# CH341A.net
KiCad netlist of a schematic drawn in Altium Designer
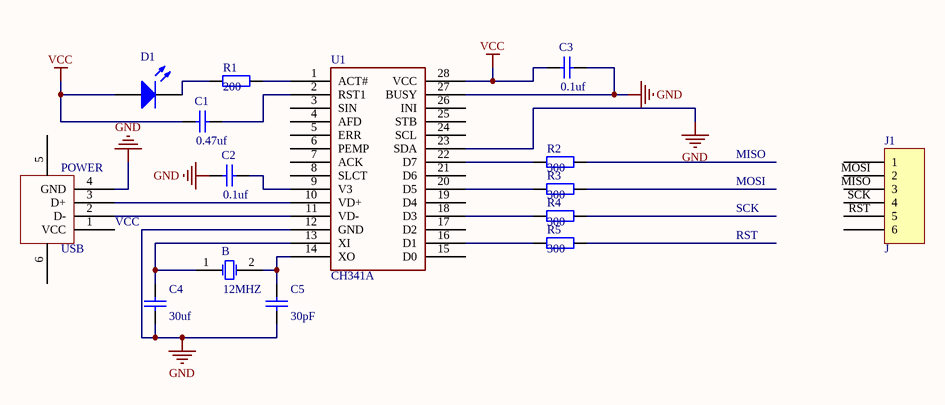
[diagram p0: CH341A.SchDoc]

(export (version "E")
  (design (tool "Eeschema 10.0.6"))
  (components
    (comp (ref "B")
      (value "12MHZ")
      (footprint "R38")
      (description "Crystal Oscillator")
      (fields (field (name "PUBLISHER") "Altium Limited"))
      (libsource (lib "Miscellaneous Devices") (part "XTAL"))
    )
    (comp (ref "C1")
      (value "0.47uf")
      (footprint "RAD-0.3")
      (description "Capacitor")
      (fields (field (name "Comment") "Cap") (field (name "PUBLISHER") "Altium Limited"))
      (libsource (lib "Miscellaneous Devices") (part "Cap"))
    )
    (comp (ref "C2")
      (value "0.1uf")
      (footprint "RAD-0.3")
      (description "Capacitor")
      (fields (field (name "Comment") "Cap") (field (name "PUBLISHER") "Altium Limited"))
      (libsource (lib "Miscellaneous Devices") (part "Cap"))
    )
    (comp (ref "C3")
      (value "0.1uf")
      (footprint "RAD-0.3")
      (description "Capacitor")
      (fields (field (name "Comment") "Cap") (field (name "PUBLISHER") "Altium Limited"))
      (libsource (lib "Miscellaneous Devices") (part "Cap"))
    )
    (comp (ref "C4")
      (value "30uf")
      (footprint "RAD-0.3")
      (description "Capacitor")
      (fields (field (name "Comment") "Cap") (field (name "PUBLISHER") "Altium Limited"))
      (libsource (lib "Miscellaneous Devices") (part "Cap"))
    )
    (comp (ref "C5")
      (value "30pF")
      (footprint "RAD-0.3")
      (description "Capacitor")
      (fields (field (name "Comment") "Cap") (field (name "PUBLISHER") "Altium Limited"))
      (libsource (lib "Miscellaneous Devices") (part "Cap"))
    )
    (comp (ref "D1")
      (value "LED0")
      (footprint "LED-0")
      (description "Typical INFRARED GaAs LED")
      (fields (field (name "PUBLISHER") "Altium Limited"))
      (libsource (lib "Miscellaneous Devices") (part "LED0"))
    )
    (comp (ref "J1") (value "J") (libsource (lib "CH341A") (part "J1")))
    (comp (ref "R1")
      (value "200")
      (footprint "AXIAL-0.4")
      (description "Resistor")
      (fields (field (name "Comment") "Res2") (field (name "PUBLISHER") "Altium Limited"))
      (libsource (lib "Miscellaneous Devices") (part "Res2"))
    )
    (comp (ref "R2")
      (value "300")
      (footprint "AXIAL-0.4")
      (description "Resistor")
      (fields (field (name "Comment") "Res2") (field (name "PUBLISHER") "Altium Limited"))
      (libsource (lib "Miscellaneous Devices") (part "Res2"))
    )
    (comp (ref "R3")
      (value "300")
      (footprint "AXIAL-0.4")
      (description "Resistor")
      (fields (field (name "Comment") "Res2") (field (name "PUBLISHER") "Altium Limited"))
      (libsource (lib "Miscellaneous Devices") (part "Res2"))
    )
    (comp (ref "R4")
      (value "300")
      (footprint "AXIAL-0.4")
      (description "Resistor")
      (fields (field (name "Comment") "Res2") (field (name "PUBLISHER") "Altium Limited"))
      (libsource (lib "Miscellaneous Devices") (part "Res2"))
    )
    (comp (ref "R5")
      (value "300")
      (footprint "AXIAL-0.4")
      (description "Resistor")
      (fields (field (name "Comment") "Res2") (field (name "PUBLISHER") "Altium Limited"))
      (libsource (lib "Miscellaneous Devices") (part "Res2"))
    )
    (comp (ref "U1") (value "CH341A") (libsource (lib "CH341A") (part "U1")))
    (comp (ref "USB") (value "POWER") (libsource (lib "CH341A") (part "POWER")))
  )
  (nets
    (net (code "1") (name "GND") (class "Default")
      (node (ref "C2") (pin "1") (pinfunction "1_1") (pintype "passive"))
      (node (ref "C3") (pin "2") (pinfunction "2_2") (pintype "passive"))
      (node (ref "C4") (pin "1") (pinfunction "1_1") (pintype "passive"))
      (node (ref "C5") (pin "1") (pinfunction "1_1") (pintype "passive"))
      (node (ref "U1") (pin "12") (pinfunction "GND_12") (pintype "passive"))
      (node (ref "U1") (pin "23") (pinfunction "SDA_23") (pintype "passive"))
      (node (ref "U1") (pin "27") (pinfunction "BUSY_27") (pintype "passive"))
      (node (ref "USB") (pin "4") (pinfunction "GND_4") (pintype "passive"))
    )
    (net (code "2") (name "Net-(B-OSC1)") (class "Default")
      (node (ref "B") (pin "1") (pinfunction "OSC1_1") (pintype "passive"))
      (node (ref "C4") (pin "2") (pinfunction "2_2") (pintype "passive"))
      (node (ref "U1") (pin "13") (pinfunction "XI_13") (pintype "passive"))
    )
    (net (code "3") (name "Net-(B-OSC2)") (class "Default")
      (node (ref "B") (pin "2") (pinfunction "OSC2_2") (pintype "passive"))
      (node (ref "C5") (pin "2") (pinfunction "2_2") (pintype "passive"))
      (node (ref "U1") (pin "14") (pinfunction "XO_14") (pintype "passive"))
    )
    (net (code "4") (name "Net-(D1-K)") (class "Default")
      (node (ref "D1") (pin "2") (pinfunction "K_2") (pintype "passive"))
      (node (ref "R1") (pin "1") (pinfunction "1_1") (pintype "passive"))
    )
    (net (code "5") (name "Net-(U1-ACT#)") (class "Default")
      (node (ref "R1") (pin "2") (pinfunction "2_2") (pintype "passive"))
      (node (ref "U1") (pin "1") (pinfunction "ACT#_1") (pintype "passive"))
    )
    (net (code "6") (name "Net-(U1-D1)") (class "Default")
      (node (ref "R5") (pin "1") (pinfunction "1_1") (pintype "passive"))
      (node (ref "U1") (pin "16") (pinfunction "D1_16") (pintype "passive"))
    )
    (net (code "7") (name "Net-(U1-D3)") (class "Default")
      (node (ref "R4") (pin "1") (pinfunction "1_1") (pintype "passive"))
      (node (ref "U1") (pin "18") (pinfunction "D3_18") (pintype "passive"))
    )
    (net (code "8") (name "Net-(U1-D5)") (class "Default")
      (node (ref "R3") (pin "1") (pinfunction "1_1") (pintype "passive"))
      (node (ref "U1") (pin "20") (pinfunction "D5_20") (pintype "passive"))
    )
    (net (code "9") (name "Net-(U1-D7)") (class "Default")
      (node (ref "R2") (pin "1") (pinfunction "1_1") (pintype "passive"))
      (node (ref "U1") (pin "22") (pinfunction "D7_22") (pintype "passive"))
    )
    (net (code "10") (name "Net-(U1-RST1)") (class "Default")
      (node (ref "C1") (pin "2") (pinfunction "2_2") (pintype "passive"))
      (node (ref "U1") (pin "2") (pinfunction "RST1_2") (pintype "passive"))
    )
    (net (code "11") (name "Net-(U1-V3)") (class "Default")
      (node (ref "C2") (pin "2") (pinfunction "2_2") (pintype "passive"))
      (node (ref "U1") (pin "9") (pinfunction "V3_9") (pintype "passive"))
    )
    (net (code "12") (name "Net-(U1-VD+)") (class "Default")
      (node (ref "U1") (pin "10") (pinfunction "VD+_10") (pintype "passive"))
      (node (ref "USB") (pin "3") (pinfunction "D+_3") (pintype "passive"))
    )
    (net (code "13") (name "Net-(U1-VD-)") (class "Default")
      (node (ref "U1") (pin "11") (pinfunction "VD-_11") (pintype "passive"))
      (node (ref "USB") (pin "2") (pinfunction "D-_2") (pintype "passive"))
    )
    (net (code "14") (name "VCC") (class "Default")
      (node (ref "C1") (pin "1") (pinfunction "1_1") (pintype "passive"))
      (node (ref "C3") (pin "1") (pinfunction "1_1") (pintype "passive"))
      (node (ref "D1") (pin "1") (pinfunction "A_1") (pintype "passive"))
      (node (ref "U1") (pin "28") (pinfunction "VCC_28") (pintype "passive"))
    )
    (net (code "15") (name "unconnected-(J1-1-Pad)") (class "Default")
      (node (ref "J1") (pin "") (pinfunction "1_") (pintype "passive"))
    )
    (net (code "16") (name "unconnected-(J1-2-PadMOSI)") (class "Default")
      (node (ref "J1") (pin "MOSI") (pinfunction "2_MOSI") (pintype "passive"))
    )
    (net (code "17") (name "unconnected-(J1-3-PadMISO)") (class "Default")
      (node (ref "J1") (pin "MISO") (pinfunction "3_MISO") (pintype "passive"))
    )
    (net (code "18") (name "unconnected-(J1-4-PadSCK)") (class "Default")
      (node (ref "J1") (pin "SCK") (pinfunction "4_SCK") (pintype "passive"))
    )
    (net (code "19") (name "unconnected-(J1-5-PadRST)") (class "Default")
      (node (ref "J1") (pin "RST") (pinfunction "5_RST") (pintype "passive"))
    )
    (net (code "20") (name "unconnected-(J1-6-Pad)") (class "Default")
      (node (ref "J1") (pin "") (pinfunction "6_") (pintype "passive"))
    )
    (net (code "21") (name "unconnected-(R2-Pad2)") (class "Default")
      (node (ref "R2") (pin "2") (pinfunction "2_2") (pintype "passive"))
    )
    (net (code "22") (name "unconnected-(R3-Pad2)") (class "Default")
      (node (ref "R3") (pin "2") (pinfunction "2_2") (pintype "passive"))
    )
    (net (code "23") (name "unconnected-(R4-Pad2)") (class "Default")
      (node (ref "R4") (pin "2") (pinfunction "2_2") (pintype "passive"))
    )
    (net (code "24") (name "unconnected-(R5-Pad2)") (class "Default")
      (node (ref "R5") (pin "2") (pinfunction "2_2") (pintype "passive"))
    )
    (net (code "25") (name "unconnected-(U1-ACK-Pad7)") (class "Default")
      (node (ref "U1") (pin "7") (pinfunction "ACK_7") (pintype "passive"))
    )
    (net (code "26") (name "unconnected-(U1-AFD-Pad4)") (class "Default")
      (node (ref "U1") (pin "4") (pinfunction "AFD_4") (pintype "passive"))
    )
    (net (code "27") (name "unconnected-(U1-D0-Pad15)") (class "Default")
      (node (ref "U1") (pin "15") (pinfunction "D0_15") (pintype "passive"))
    )
    (net (code "28") (name "unconnected-(U1-D2-Pad17)") (class "Default")
      (node (ref "U1") (pin "17") (pinfunction "D2_17") (pintype "passive"))
    )
    (net (code "29") (name "unconnected-(U1-D4-Pad19)") (class "Default")
      (node (ref "U1") (pin "19") (pinfunction "D4_19") (pintype "passive"))
    )
    (net (code "30") (name "unconnected-(U1-D6-Pad21)") (class "Default")
      (node (ref "U1") (pin "21") (pinfunction "D6_21") (pintype "passive"))
    )
    (net (code "31") (name "unconnected-(U1-ERR-Pad5)") (class "Default")
      (node (ref "U1") (pin "5") (pinfunction "ERR_5") (pintype "passive"))
    )
    (net (code "32") (name "unconnected-(U1-INI-Pad26)") (class "Default")
      (node (ref "U1") (pin "26") (pinfunction "INI_26") (pintype "passive"))
    )
    (net (code "33") (name "unconnected-(U1-PEMP-Pad6)") (class "Default")
      (node (ref "U1") (pin "6") (pinfunction "PEMP_6") (pintype "passive"))
    )
    (net (code "34") (name "unconnected-(U1-SCL-Pad24)") (class "Default")
      (node (ref "U1") (pin "24") (pinfunction "SCL_24") (pintype "passive"))
    )
    (net (code "35") (name "unconnected-(U1-SIN-Pad3)") (class "Default")
      (node (ref "U1") (pin "3") (pinfunction "SIN_3") (pintype "passive"))
    )
    (net (code "36") (name "unconnected-(U1-SLCT-Pad8)") (class "Default")
      (node (ref "U1") (pin "8") (pinfunction "SLCT_8") (pintype "passive"))
    )
    (net (code "37") (name "unconnected-(U1-STB-Pad25)") (class "Default")
      (node (ref "U1") (pin "25") (pinfunction "STB_25") (pintype "passive"))
    )
    (net (code "38") (name "unconnected-(USB-Pad5)") (class "Default")
      (node (ref "USB") (pin "5") (pinfunction "5_5") (pintype "passive"))
    )
    (net (code "39") (name "unconnected-(USB-Pad6)") (class "Default")
      (node (ref "USB") (pin "6") (pinfunction "6_6") (pintype "passive"))
    )
    (net (code "40") (name "unconnected-(USB-VCC-Pad1)") (class "Default")
      (node (ref "USB") (pin "1") (pinfunction "VCC_1") (pintype "passive"))
    )
  )
)
